# SCH.net
KiCad netlist of a schematic drawn in Altium Designer
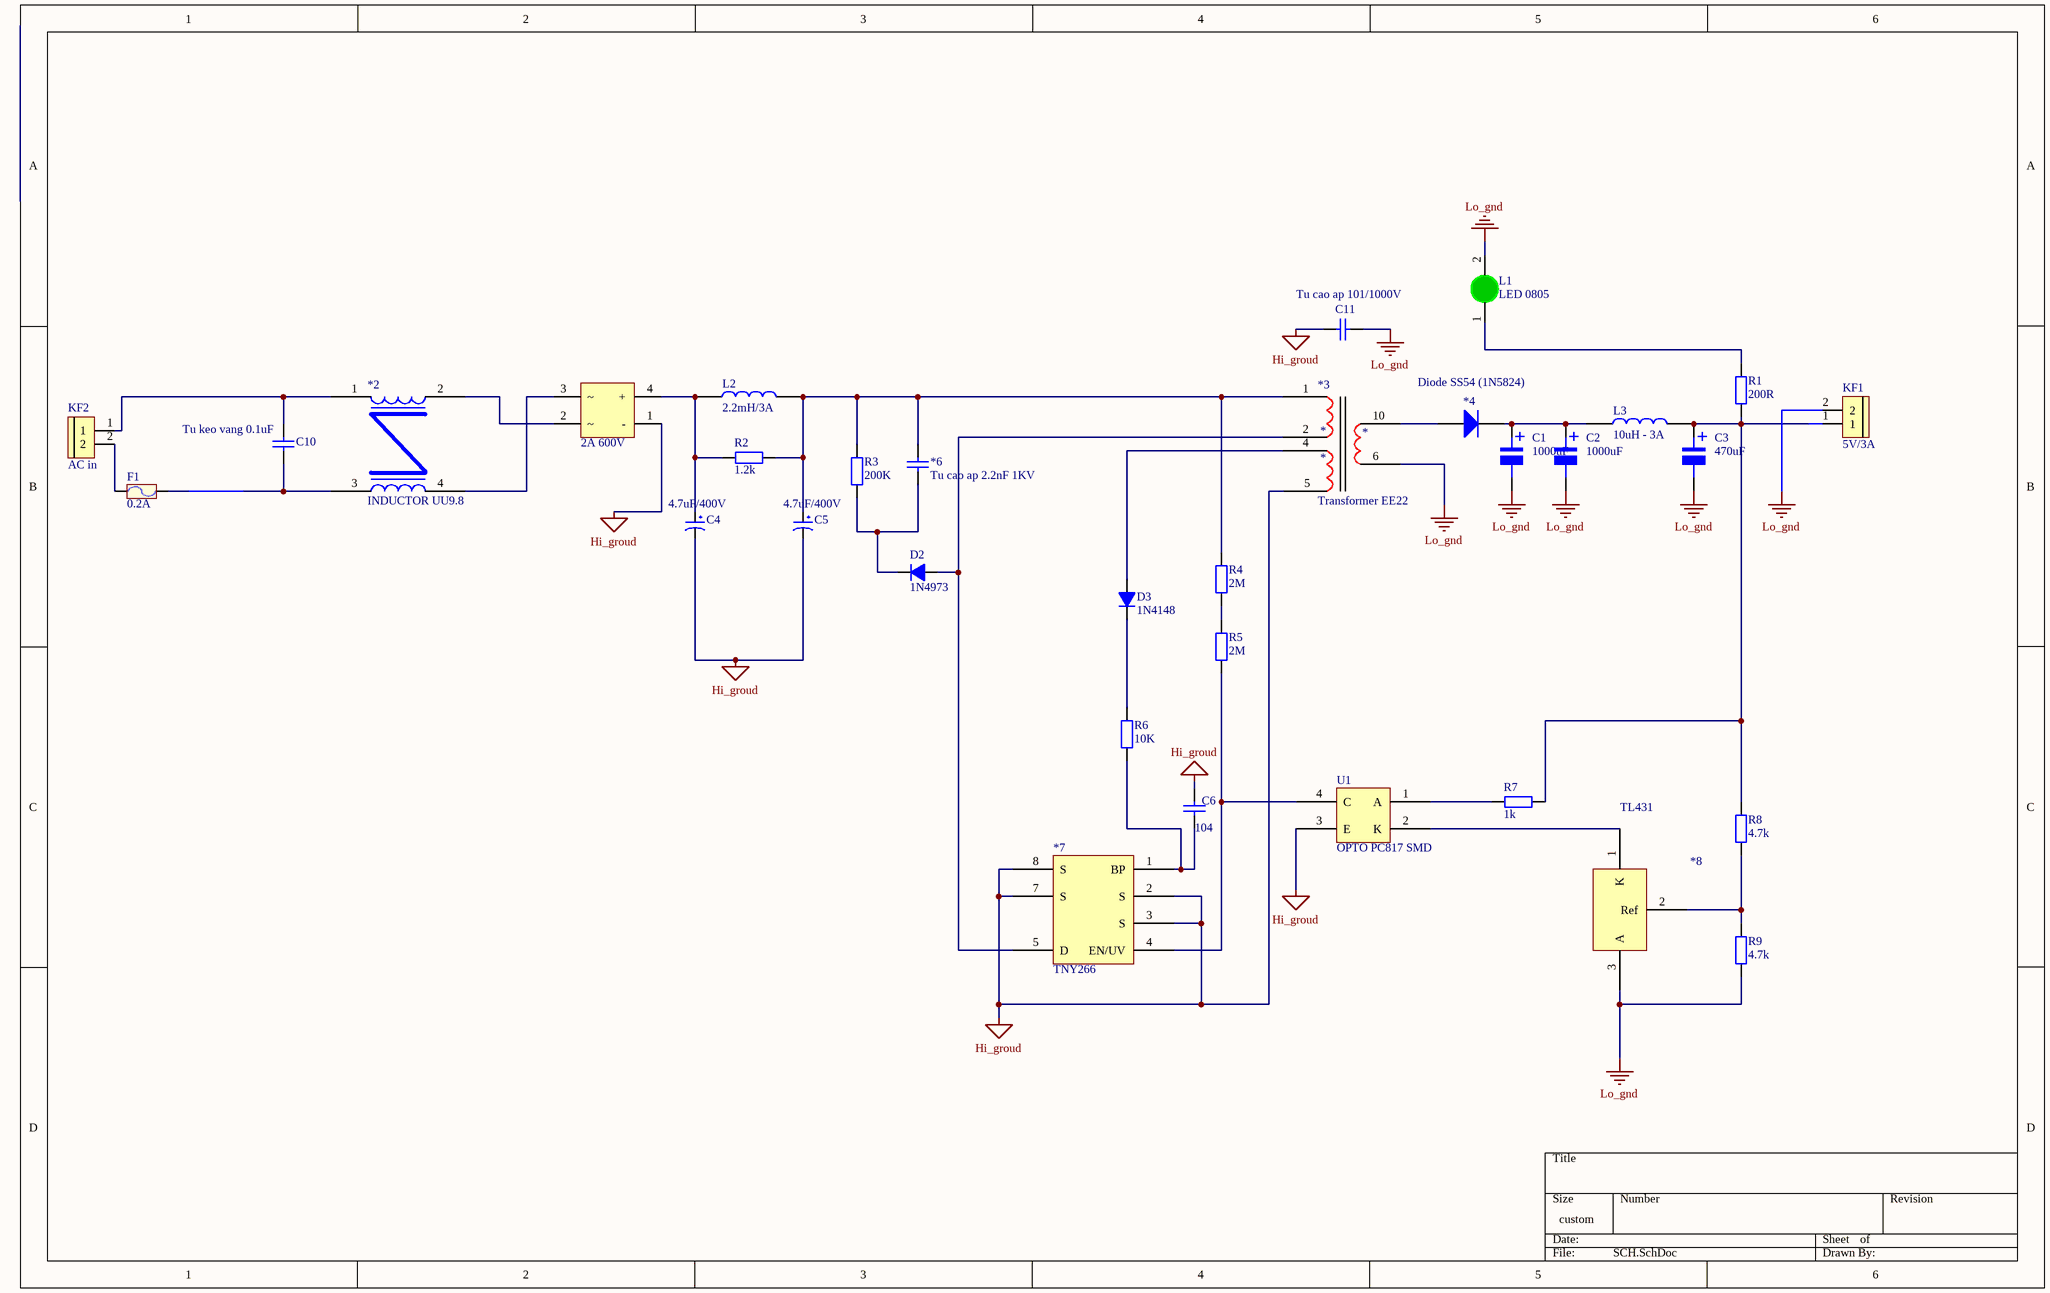
[diagram p0: SCH.SchDoc]

(export (version "E")
  (design (tool "Eeschema 10.0.6"))
  (components
    (comp (ref "*2")
      (value "INDUCTOR UU9.8")
      (footprint "INDUCTOR UU9.8")
      (libsource (lib "TrungVan_Lib") (part "INDUCTOR UU9.8"))
    )
    (comp (ref "*3")
      (value "Transformer EE22")
      (footprint "TRANSFORMER EE22")
      (libsource (lib "TrungVan_Lib") (part "Transformer EE22"))
    )
    (comp (ref "*4")
      (value "Diode SS54 (1N5824)")
      (footprint "DIODE SMA")
      (libsource (lib "TrungVan_Lib") (part "Diode SS54 (1N5824)"))
    )
    (comp (ref "*6")
      (value "Tu cao ap 2.2nF 1KV")
      (footprint "Tu cao ap")
      (libsource (lib "TrungVan_Lib") (part "Tu cao ap 2.2nF 1KV"))
    )
    (comp (ref "*7") (value "TNY266") (footprint "DIP8") (libsource (lib "TrungVan_Lib") (part "TNY264")))
    (comp (ref "*8")
      (value "TL431")
      (footprint "TL431 SOT-23-3")
      (libsource (lib "TrungVan_Lib") (part "TL431"))
    )
    (comp (ref "C1")
      (value "1000uF")
      (footprint "tu nhom 10 (G)")
      (description "Dán")
      (libsource (lib "TrungVan_Lib") (part "Tu Nhom 1000uF 10V"))
    )
    (comp (ref "C2")
      (value "1000uF")
      (footprint "tu nhom 10 (G)")
      (description "Dán")
      (libsource (lib "TrungVan_Lib") (part "Tu Nhom 1000uF 10V"))
    )
    (comp (ref "C3")
      (value "470uF")
      (footprint "tu nhom 8 (f)")
      (description "Dán")
      (libsource (lib "TrungVan_Lib") (part "Tu Nhom 470uF 16V"))
    )
    (comp (ref "C4")
      (value "4.7uF/400V")
      (footprint "tu hoa 8mm")
      (description "Cắm")
      (libsource (lib "TrungVan_Lib") (part "Tu Hoa 4.7uF 400V 8x12"))
    )
    (comp (ref "C5")
      (value "4.7uF/400V")
      (footprint "tu hoa 8mm")
      (description "Cắm")
      (libsource (lib "TrungVan_Lib") (part "Tu Hoa 4.7uF 400V 8x12"))
    )
    (comp (ref "C6")
      (value "104")
      (footprint "tu 1206")
      (description "Dán")
      (libsource (lib "TrungVan_Lib") (part "Tu 1206 104 50V 20%"))
    )
    (comp (ref "C10")
      (value "Tu keo vang 0.1uF")
      (footprint "Tu keo vang 0.1uF")
      (libsource (lib "TrungVan_Lib") (part "Tu keo vang 0.1uF"))
    )
    (comp (ref "C11")
      (value "Tu cao ap 101/1000V")
      (footprint "Tu cao ap")
      (libsource (lib "TrungVan_Lib") (part "Tu cao ap 1000V"))
    )
    (comp (ref "D1")
      (value "2A 600V")
      (footprint "DIODE CAU 2A 3A CAM")
      (description "Cắm")
      (libsource (lib "TrungVan_Lib") (part "Diode CAU 2A VUONG"))
    )
    (comp (ref "D2")
      (value "1N4973")
      (footprint "DIODE 1A")
      (description "Cắm")
      (libsource (lib "TrungVan_Lib") (part "Diode 1N4007"))
    )
    (comp (ref "D3")
      (value "1N4148")
      (footprint "DIODE 0.5A")
      (description "Cắm")
      (libsource (lib "TrungVan_Lib") (part "Diode 1N4148"))
    )
    (comp (ref "F1")
      (value "0.2A")
      (footprint "De Cau Chi 520 630")
      (description "5x20mm")
      (libsource (lib "TrungVan_Lib") (part "De Cau Chi 520 630"))
    )
    (comp (ref "KF1")
      (value "5V/3A")
      (footprint "Con 2 KF301 5.08")
      (description "Cắm")
      (libsource (lib "") (part "CON 2 KF301_1"))
    )
    (comp (ref "KF2")
      (value "AC in")
      (footprint "Con 2 KF301 5.08")
      (description "Cắm")
      (libsource (lib "TrungVan_Lib") (part "CON 2 KF301"))
    )
    (comp (ref "L1")
      (value "LED 0805")
      (footprint "LED-1206-Green")
      (description "Dán")
      (libsource (lib "TrungVan_Lib") (part "LED 1206 Xanh La"))
    )
    (comp (ref "L2")
      (value "2.2mH/3A")
      (footprint "CUON CAM 100uH3A")
      (description "Cắm")
      (libsource (lib "TrungVan_Lib") (part "CUON CAM 470uH DIP"))
    )
    (comp (ref "L3")
      (value "10uH - 3A")
      (footprint "CUON CAM 100uH3A")
      (description "Cắm")
      (libsource (lib "TrungVan_Lib") (part "CUON CAM 470uH DIP"))
    )
    (comp (ref "R1")
      (value "200R")
      (footprint "tro smd 1206")
      (description "Dán")
      (libsource (lib "TrungVan_Lib") (part "Tro 1206 1% 200R"))
    )
    (comp (ref "R2")
      (value "1.2k")
      (footprint "tro smd 1206")
      (description "Dán")
      (libsource (lib "TrungVan_Lib") (part "Tro 1206 1% 1k"))
    )
    (comp (ref "R3")
      (value "200K")
      (footprint "Dien tro")
      (description "Cắm")
      (libsource (lib "TrungVan_Lib") (part "Resistor"))
    )
    (comp (ref "R4")
      (value "2M")
      (footprint "Dien tro")
      (description "Cắm")
      (libsource (lib "TrungVan_Lib") (part "Resistor"))
    )
    (comp (ref "R5")
      (value "2M")
      (footprint "Dien tro")
      (description "Cắm")
      (libsource (lib "TrungVan_Lib") (part "Resistor"))
    )
    (comp (ref "R6")
      (value "10K")
      (footprint "Dien tro")
      (description "Cắm")
      (libsource (lib "TrungVan_Lib") (part "Resistor"))
    )
    (comp (ref "R7")
      (value "1k")
      (footprint "tro smd 1206")
      (description "Dán")
      (libsource (lib "TrungVan_Lib") (part "Tro 1206 1% 1k"))
    )
    (comp (ref "R8")
      (value "4.7k")
      (footprint "tro smd 1206")
      (description "Dán")
      (libsource (lib "TrungVan_Lib") (part "Tro 1206 5% 4.7K"))
    )
    (comp (ref "R9")
      (value "4.7k")
      (footprint "tro smd 1206")
      (description "Dán")
      (libsource (lib "TrungVan_Lib") (part "Tro 1206 5% 4.7K"))
    )
    (comp (ref "U1")
      (value "OPTO PC817 SMD")
      (footprint "SOP4")
      (description "Single Opto")
      (libsource (lib "TrungVan_Lib") (part "OPTO PC817 SMD"))
    )
  )
  (nets
    (net (code "1") (name "Hi_groud") (class "Default")
      (node (ref "*3") (pin "5") (pinfunction "5_5") (pintype "passive"))
      (node (ref "*7") (pin "2") (pinfunction "S_2") (pintype "passive"))
      (node (ref "*7") (pin "3") (pinfunction "S_3") (pintype "passive"))
      (node (ref "*7") (pin "7") (pinfunction "S_7") (pintype "passive"))
      (node (ref "*7") (pin "8") (pinfunction "S_8") (pintype "passive"))
      (node (ref "C11") (pin "2") (pinfunction "2_2") (pintype "passive"))
      (node (ref "C4") (pin "2") (pinfunction "2_2") (pintype "passive"))
      (node (ref "C5") (pin "2") (pinfunction "2_2") (pintype "passive"))
      (node (ref "C6") (pin "1") (pinfunction "1_1") (pintype "passive"))
      (node (ref "D1") (pin "1") (pinfunction "-_1") (pintype "passive"))
      (node (ref "U1") (pin "3") (pinfunction "E_3") (pintype "passive"))
    )
    (net (code "2") (name "Lo_gnd") (class "Default")
      (node (ref "*3") (pin "6") (pinfunction "6_6") (pintype "passive"))
      (node (ref "*8") (pin "3") (pinfunction "A_3") (pintype "passive"))
      (node (ref "C1") (pin "2") (pinfunction "2_2") (pintype "passive"))
      (node (ref "C11") (pin "1") (pinfunction "1_1") (pintype "passive"))
      (node (ref "C2") (pin "2") (pinfunction "2_2") (pintype "passive"))
      (node (ref "C3") (pin "2") (pinfunction "2_2") (pintype "passive"))
      (node (ref "KF1") (pin "2") (pinfunction "2_2") (pintype "passive"))
      (node (ref "L1") (pin "2") (pinfunction "K_2") (pintype "passive"))
      (node (ref "R9") (pin "1") (pinfunction "1_1") (pintype "passive"))
    )
    (net (code "3") (name "Net-(*2-Pad1)") (class "Default")
      (node (ref "*2") (pin "1") (pinfunction "1_1") (pintype "passive"))
      (node (ref "C10") (pin "1") (pinfunction "1_1") (pintype "passive"))
      (node (ref "KF2") (pin "1") (pinfunction "1_1") (pintype "passive"))
    )
    (net (code "4") (name "Net-(*2-Pad2)") (class "Default")
      (node (ref "*2") (pin "2") (pinfunction "2_2") (pintype "passive"))
      (node (ref "D1") (pin "2") (pinfunction "~_2") (pintype "passive"))
    )
    (net (code "5") (name "Net-(*2-Pad3)") (class "Default")
      (node (ref "*2") (pin "3") (pinfunction "3_3") (pintype "passive"))
      (node (ref "C10") (pin "2") (pinfunction "2_2") (pintype "passive"))
      (node (ref "F1") (pin "1") (pinfunction "1_1") (pintype "passive"))
    )
    (net (code "6") (name "Net-(*2-Pad4)") (class "Default")
      (node (ref "*2") (pin "4") (pinfunction "4_4") (pintype "passive"))
      (node (ref "D1") (pin "3") (pinfunction "~_3") (pintype "passive"))
    )
    (net (code "7") (name "Net-(*3-Pad1)") (class "Default")
      (node (ref "*3") (pin "1") (pinfunction "1_1") (pintype "passive"))
      (node (ref "*6") (pin "1") (pinfunction "1_1") (pintype "passive"))
      (node (ref "C5") (pin "1") (pinfunction "1_1") (pintype "passive"))
      (node (ref "L2") (pin "2") (pinfunction "2_2") (pintype "passive"))
      (node (ref "R2") (pin "2") (pinfunction "2_2") (pintype "passive"))
      (node (ref "R3") (pin "2") (pinfunction "2_2") (pintype "passive"))
      (node (ref "R4") (pin "2") (pinfunction "2_2") (pintype "passive"))
    )
    (net (code "8") (name "Net-(*4-A)") (class "Default")
      (node (ref "*3") (pin "10") (pinfunction "10_10") (pintype "passive"))
      (node (ref "*4") (pin "1") (pinfunction "A_1") (pintype "passive"))
    )
    (net (code "9") (name "Net-(*4-K)") (class "Default")
      (node (ref "*4") (pin "2") (pinfunction "K_2") (pintype "passive"))
      (node (ref "C1") (pin "1") (pinfunction "1_1") (pintype "passive"))
      (node (ref "C2") (pin "1") (pinfunction "1_1") (pintype "passive"))
      (node (ref "L3") (pin "1") (pinfunction "1_1") (pintype "passive"))
    )
    (net (code "10") (name "Net-(*7-BP)") (class "Default")
      (node (ref "*7") (pin "1") (pinfunction "BP_1") (pintype "passive"))
      (node (ref "C6") (pin "2") (pinfunction "2_2") (pintype "passive"))
      (node (ref "R6") (pin "1") (pinfunction "1_1") (pintype "passive"))
    )
    (net (code "11") (name "Net-(*7-D)") (class "Default")
      (node (ref "*3") (pin "2") (pinfunction "2_2") (pintype "passive"))
      (node (ref "*7") (pin "5") (pinfunction "D_5") (pintype "passive"))
      (node (ref "D2") (pin "1") (pinfunction "A_1") (pintype "passive"))
    )
    (net (code "12") (name "Net-(*7-EN{slash}UV)") (class "Default")
      (node (ref "*7") (pin "4") (pinfunction "EN/UV_4") (pintype "passive"))
      (node (ref "R5") (pin "1") (pinfunction "1_1") (pintype "passive"))
      (node (ref "U1") (pin "4") (pinfunction "C_4") (pintype "passive"))
    )
    (net (code "13") (name "Net-(*8-K)") (class "Default")
      (node (ref "*8") (pin "1") (pinfunction "K_1") (pintype "passive"))
      (node (ref "U1") (pin "2") (pinfunction "K_2") (pintype "passive"))
    )
    (net (code "14") (name "Net-(*8-Ref)") (class "Default")
      (node (ref "*8") (pin "2") (pinfunction "Ref_2") (pintype "passive"))
      (node (ref "R8") (pin "1") (pinfunction "1_1") (pintype "passive"))
      (node (ref "R9") (pin "2") (pinfunction "2_2") (pintype "passive"))
    )
    (net (code "15") (name "Net-(C3-Pad1)") (class "Default")
      (node (ref "C3") (pin "1") (pinfunction "1_1") (pintype "passive"))
      (node (ref "KF1") (pin "1") (pinfunction "1_1") (pintype "passive"))
      (node (ref "L3") (pin "2") (pinfunction "2_2") (pintype "passive"))
      (node (ref "R1") (pin "2") (pinfunction "2_2") (pintype "passive"))
      (node (ref "R7") (pin "2") (pinfunction "2_2") (pintype "passive"))
      (node (ref "R8") (pin "2") (pinfunction "2_2") (pintype "passive"))
    )
    (net (code "16") (name "Net-(D1-+)") (class "Default")
      (node (ref "C4") (pin "1") (pinfunction "1_1") (pintype "passive"))
      (node (ref "D1") (pin "4") (pinfunction "+_4") (pintype "passive"))
      (node (ref "L2") (pin "1") (pinfunction "1_1") (pintype "passive"))
      (node (ref "R2") (pin "1") (pinfunction "1_1") (pintype "passive"))
    )
    (net (code "17") (name "Net-(D2-K)") (class "Default")
      (node (ref "*6") (pin "2") (pinfunction "2_2") (pintype "passive"))
      (node (ref "D2") (pin "2") (pinfunction "K_2") (pintype "passive"))
      (node (ref "R3") (pin "1") (pinfunction "1_1") (pintype "passive"))
    )
    (net (code "18") (name "Net-(D3-A)") (class "Default")
      (node (ref "*3") (pin "4") (pinfunction "4_4") (pintype "passive"))
      (node (ref "D3") (pin "1") (pinfunction "A_1") (pintype "passive"))
    )
    (net (code "19") (name "Net-(D3-K)") (class "Default")
      (node (ref "D3") (pin "2") (pinfunction "K_2") (pintype "passive"))
      (node (ref "R6") (pin "2") (pinfunction "2_2") (pintype "passive"))
    )
    (net (code "20") (name "Net-(F1-Pad2)") (class "Default")
      (node (ref "F1") (pin "2") (pinfunction "2_2") (pintype "passive"))
      (node (ref "KF2") (pin "2") (pinfunction "2_2") (pintype "passive"))
    )
    (net (code "21") (name "Net-(L1-A)") (class "Default")
      (node (ref "L1") (pin "1") (pinfunction "A_1") (pintype "passive"))
      (node (ref "R1") (pin "1") (pinfunction "1_1") (pintype "passive"))
    )
    (net (code "22") (name "Net-(R4-Pad1)") (class "Default")
      (node (ref "R4") (pin "1") (pinfunction "1_1") (pintype "passive"))
      (node (ref "R5") (pin "2") (pinfunction "2_2") (pintype "passive"))
    )
    (net (code "23") (name "Net-(U1-A)") (class "Default")
      (node (ref "R7") (pin "1") (pinfunction "1_1") (pintype "passive"))
      (node (ref "U1") (pin "1") (pinfunction "A_1") (pintype "passive"))
    )
  )
)
